# SparkFun_Buck_Regulator_Breakout_-_AP632.net
KiCad netlist of a schematic drawn in EAGLE
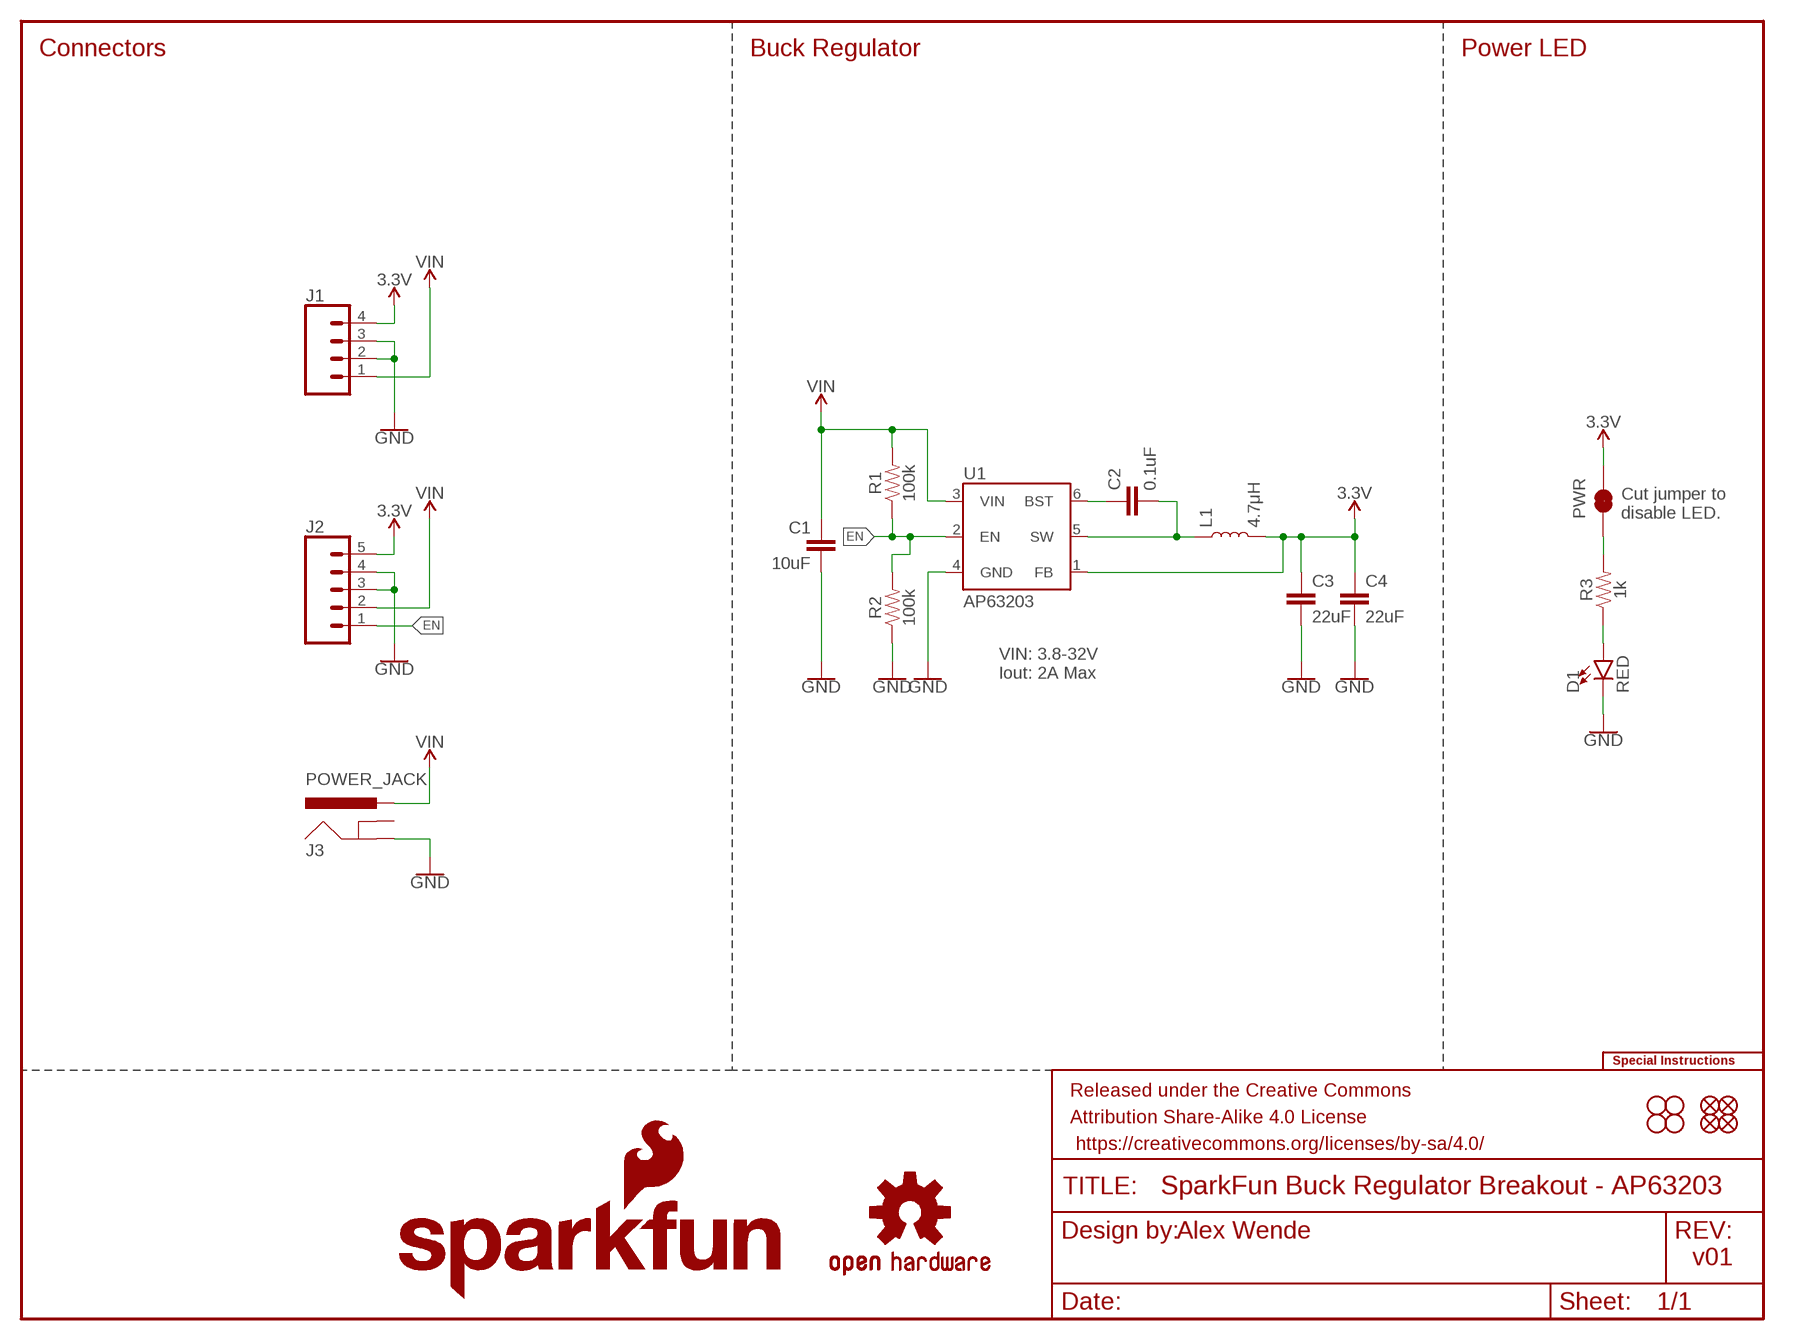
[diagram p0: schematic, sheet 1]

(export (version "E")
  (design (tool "Eeschema 10.0.6"))
  (components
    (comp (ref "C1")
      (value "10uF")
      (footprint "eagle-import:1210")
      (libsource (lib "eagle-import") (part "10UF-1210-50V-20%"))
    )
    (comp (ref "C2")
      (value "0.1uF")
      (footprint "eagle-import:0603")
      (libsource (lib "eagle-import") (part "0.1UF-0603-25V-5%"))
    )
    (comp (ref "C3")
      (value "22uF")
      (footprint "eagle-import:0603")
      (libsource (lib "eagle-import") (part "22UF-0603-6.3V-20%"))
    )
    (comp (ref "C4")
      (value "22uF")
      (footprint "eagle-import:0603")
      (libsource (lib "eagle-import") (part "22UF-0603-6.3V-20%"))
    )
    (comp (ref "D1")
      (value "RED")
      (footprint "eagle-import:LED-0603")
      (libsource (lib "eagle-import") (part "LED-RED0603"))
    )
    (comp (ref "FD1")
      (value "FIDUCIALUFIDUCIAL")
      (footprint "eagle-import:FIDUCIAL-MICRO")
      (libsource (lib "eagle-import") (part "FIDUCIALUFIDUCIAL"))
    )
    (comp (ref "FD2")
      (value "FIDUCIALUFIDUCIAL")
      (footprint "eagle-import:FIDUCIAL-MICRO")
      (libsource (lib "eagle-import") (part "FIDUCIALUFIDUCIAL"))
    )
    (comp (ref "FD3")
      (value "FIDUCIALUFIDUCIAL")
      (footprint "eagle-import:FIDUCIAL-MICRO")
      (libsource (lib "eagle-import") (part "FIDUCIALUFIDUCIAL"))
    )
    (comp (ref "FD4")
      (value "FIDUCIALUFIDUCIAL")
      (footprint "eagle-import:FIDUCIAL-MICRO")
      (libsource (lib "eagle-import") (part "FIDUCIALUFIDUCIAL"))
    )
    (comp (ref "FRAME1")
      (value "FRAME-LETTER")
      (footprint "eagle-import:CREATIVE_COMMONS")
      (libsource (lib "eagle-import") (part "FRAME-LETTER"))
    )
    (comp (ref "H1")
      (value "STAND-OFF")
      (footprint "eagle-import:STAND-OFF")
      (libsource (lib "eagle-import") (part "STAND-OFF"))
    )
    (comp (ref "H2")
      (value "STAND-OFF")
      (footprint "eagle-import:STAND-OFF")
      (libsource (lib "eagle-import") (part "STAND-OFF"))
    )
    (comp (ref "H3")
      (value "STAND-OFF")
      (footprint "eagle-import:STAND-OFF")
      (libsource (lib "eagle-import") (part "STAND-OFF"))
    )
    (comp (ref "H4")
      (value "STAND-OFF")
      (footprint "eagle-import:STAND-OFF")
      (libsource (lib "eagle-import") (part "STAND-OFF"))
    )
    (comp (ref "J1")
      (value "CONN_04SCREW")
      (footprint "eagle-import:SCREWTERMINAL-3.5MM-4")
      (libsource (lib "eagle-import") (part "CONN_04SCREW"))
    )
    (comp (ref "J2")
      (value "CONN_05NO_SILK")
      (footprint "eagle-import:1X05_NO_SILK")
      (libsource (lib "eagle-import") (part "CONN_05NO_SILK"))
    )
    (comp (ref "J3")
      (value "POWER_JACK")
      (footprint "eagle-import:POWER_JACK_PTH_SLOT")
      (libsource (lib "eagle-import") (part "POWER_JACKPOWER_JACK_SLOT"))
    )
    (comp (ref "L1")
      (value "4.7μH")
      (footprint "eagle-import:INDUCTOR_4X4MM")
      (libsource (lib "eagle-import") (part "4.7μH_SHIELDED_INDUCTORNPIS_LS"))
    )
    (comp (ref "LOGO1")
      (value "SFE_LOGO_NAME_FLAME.1_INCH")
      (footprint "eagle-import:SFE_LOGO_NAME_FLAME_.1")
      (libsource (lib "eagle-import") (part "SFE_LOGO_NAME_FLAME.1_INCH"))
    )
    (comp (ref "LOGO2")
      (value "OSHW-LOGOS")
      (footprint "eagle-import:OSHW-LOGO-S")
      (libsource (lib "eagle-import") (part "OSHW-LOGOS"))
    )
    (comp (ref "LOGO3")
      (value "SPECIAL_INSTRUCTIONS-ORDERING")
      (footprint "eagle-import:ORDERING_INSTRUCTIONS")
      (libsource (lib "eagle-import") (part "SPECIAL_INSTRUCTIONS-ORDERING"))
    )
    (comp (ref "PWR")
      (value "JUMPER-SMT_2_NC_TRACE_SILK")
      (footprint "eagle-import:SMT-JUMPER_2_NC_TRACE_SILK")
      (libsource (lib "eagle-import") (part "JUMPER-SMT_2_NC_TRACE_SILK"))
    )
    (comp (ref "R1")
      (value "100k")
      (footprint "eagle-import:0603")
      (libsource (lib "eagle-import") (part "100KOHM-0603-1/10W-1%"))
    )
    (comp (ref "R2")
      (value "100k")
      (footprint "eagle-import:0603")
      (libsource (lib "eagle-import") (part "100KOHM-0603-1/10W-1%"))
    )
    (comp (ref "R3")
      (value "1k")
      (footprint "eagle-import:0603")
      (libsource (lib "eagle-import") (part "1KOHM-0603-1/10W-1%"))
    )
    (comp (ref "U1")
      (value "AP63203")
      (footprint "eagle-import:SOT23-6")
      (libsource (lib "eagle-import") (part "AP63203"))
    )
  )
  (nets
    (net (code "1") (name "3.3V") (class "Default")
      (node (ref "C3") (pin "1") (pinfunction "1_1") (pintype "passive"))
      (node (ref "C4") (pin "1") (pinfunction "1_1") (pintype "passive"))
      (node (ref "J1") (pin "4") (pinfunction "4_4") (pintype "passive"))
      (node (ref "J2") (pin "5") (pinfunction "5_5") (pintype "passive"))
      (node (ref "L1") (pin "P$2") (pinfunction "2_P$2") (pintype "passive"))
      (node (ref "PWR") (pin "2") (pinfunction "2_2") (pintype "passive"))
      (node (ref "U1") (pin "1") (pinfunction "FB_1") (pintype "bidirectional"))
    )
    (net (code "2") (name "EN") (class "Default")
      (node (ref "J2") (pin "1") (pinfunction "1_1") (pintype "passive"))
      (node (ref "R1") (pin "1") (pinfunction "1_1") (pintype "passive"))
      (node (ref "R2") (pin "2") (pinfunction "2_2") (pintype "passive"))
      (node (ref "U1") (pin "2") (pinfunction "EN_2") (pintype "bidirectional"))
    )
    (net (code "3") (name "GND") (class "Default")
      (node (ref "C1") (pin "2") (pinfunction "2_2") (pintype "passive"))
      (node (ref "C3") (pin "2") (pinfunction "2_2") (pintype "passive"))
      (node (ref "C4") (pin "2") (pinfunction "2_2") (pintype "passive"))
      (node (ref "D1") (pin "C") (pinfunction "C_C") (pintype "passive"))
      (node (ref "J1") (pin "2") (pinfunction "2_2") (pintype "passive"))
      (node (ref "J1") (pin "3") (pinfunction "3_3") (pintype "passive"))
      (node (ref "J2") (pin "3") (pinfunction "3_3") (pintype "passive"))
      (node (ref "J2") (pin "4") (pinfunction "4_4") (pintype "passive"))
      (node (ref "J3") (pin "GND") (pinfunction "GND_GND") (pintype "bidirectional"))
      (node (ref "R2") (pin "1") (pinfunction "1_1") (pintype "passive"))
      (node (ref "U1") (pin "4") (pinfunction "GND_4") (pintype "bidirectional"))
    )
    (net (code "4") (name "Net-(D1-PadA)") (class "Default")
      (node (ref "D1") (pin "A") (pinfunction "A_A") (pintype "passive"))
      (node (ref "R3") (pin "1") (pinfunction "1_1") (pintype "passive"))
    )
    (net (code "5") (name "Net-(L1-1)") (class "Default")
      (node (ref "C2") (pin "2") (pinfunction "2_2") (pintype "passive"))
      (node (ref "L1") (pin "P$1") (pinfunction "1_P$1") (pintype "passive"))
      (node (ref "U1") (pin "5") (pinfunction "SW_5") (pintype "bidirectional"))
    )
    (net (code "6") (name "Net-(PWR-Pad1)") (class "Default")
      (node (ref "PWR") (pin "1") (pinfunction "1_1") (pintype "passive"))
      (node (ref "R3") (pin "2") (pinfunction "2_2") (pintype "passive"))
    )
    (net (code "7") (name "Net-(U1-BST)") (class "Default")
      (node (ref "C2") (pin "1") (pinfunction "1_1") (pintype "passive"))
      (node (ref "U1") (pin "6") (pinfunction "BST_6") (pintype "bidirectional"))
    )
    (net (code "8") (name "VIN") (class "Default")
      (node (ref "C1") (pin "1") (pinfunction "1_1") (pintype "passive"))
      (node (ref "J1") (pin "1") (pinfunction "1_1") (pintype "passive"))
      (node (ref "J2") (pin "2") (pinfunction "2_2") (pintype "passive"))
      (node (ref "J3") (pin "PWR") (pinfunction "PWR_PWR") (pintype "bidirectional"))
      (node (ref "R1") (pin "2") (pinfunction "2_2") (pintype "passive"))
      (node (ref "U1") (pin "3") (pinfunction "VIN_3") (pintype "bidirectional"))
    )
    (net (code "9") (name "unconnected-(J3-PadGNDBREAK)") (class "Default")
      (node (ref "J3") (pin "GNDBREAK") (pinfunction "GNDBREAK_GNDBREAK") (pintype "bidirectional"))
    )
  )
)
